# Sheet1.net
KiCad netlist of a schematic drawn in Altium Designer
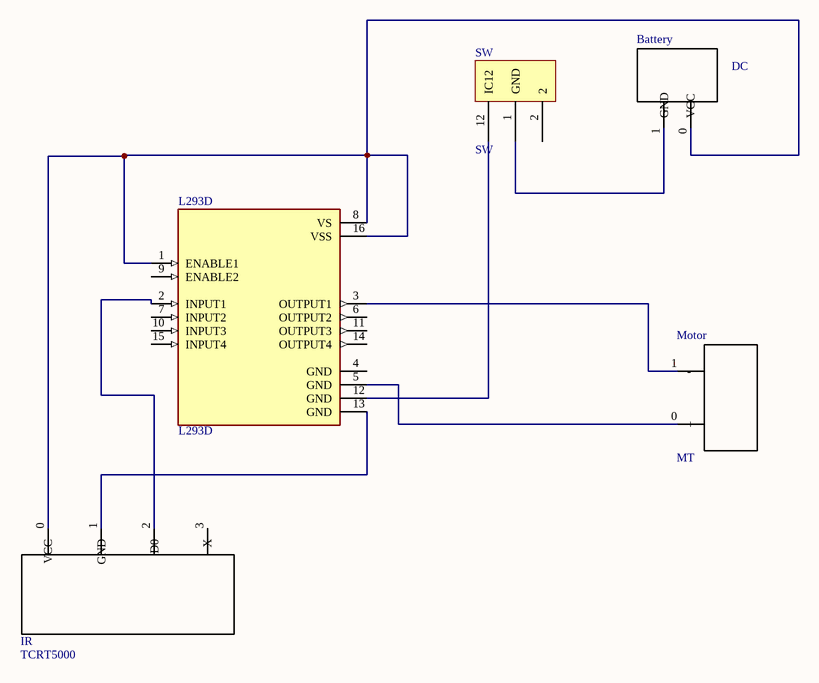
[diagram p0: Sheet1.SchDoc]

(export (version "E")
  (design (tool "Eeschema 10.0.6"))
  (components
    (comp (ref "Battery") (value "DC") (footprint "Battery") (libsource (lib "Schlib1") (part "battery")))
    (comp (ref "IR") (value "TCRT5000") (footprint "IR") (libsource (lib "Schlib1") (part "TCRT5000")))
    (comp (ref "L293D")
      (value "L293D")
      (footprint "DIP880W50P254L2000H510Q16")
      (description "Bipolar Motor Driver - Parallel 16-PowerDIP")
      (fields (field (name "MF") "STMicroelectronics"))
      (libsource (lib "Schlib1") (part "L293D"))
    )
    (comp (ref "Motor") (value "MT") (footprint "motor") (libsource (lib "Schlib1") (part "motor")))
    (comp (ref "SW") (value "SW") (footprint "SW") (libsource (lib "Schlib1") (part "SW")))
  )
  (nets
    (net (code "1") (name "Net-(Battery-GND)") (class "Default")
      (node (ref "Battery") (pin "1") (pinfunction "GND_1") (pintype "passive"))
      (node (ref "SW") (pin "1") (pinfunction "GND_1") (pintype "passive"))
    )
    (net (code "2") (name "Net-(Battery-VCC)") (class "Default")
      (node (ref "Battery") (pin "0") (pinfunction "VCC_0") (pintype "passive"))
      (node (ref "IR") (pin "0") (pinfunction "VCC_0") (pintype "power_in"))
      (node (ref "L293D") (pin "1") (pinfunction "ENABLE1_1") (pintype "input"))
      (node (ref "L293D") (pin "16") (pinfunction "VSS_16") (pintype "power_in"))
      (node (ref "L293D") (pin "8") (pinfunction "VS_8") (pintype "power_in"))
    )
    (net (code "3") (name "Net-(IR-D0)") (class "Default")
      (node (ref "IR") (pin "2") (pinfunction "D0_2") (pintype "output"))
      (node (ref "L293D") (pin "2") (pinfunction "INPUT1_2") (pintype "input"))
    )
    (net (code "4") (name "Net-(IR-GND)") (class "Default")
      (node (ref "IR") (pin "1") (pinfunction "GND_1") (pintype "power_in"))
      (node (ref "L293D") (pin "13") (pinfunction "GND_13") (pintype "power_in"))
    )
    (net (code "5") (name "Net-(L293D-OUTPUT1)") (class "Default")
      (node (ref "L293D") (pin "3") (pinfunction "OUTPUT1_3") (pintype "output"))
      (node (ref "Motor") (pin "1") (pinfunction "-_1") (pintype "passive"))
    )
    (net (code "6") (name "Net-(Motor-+)") (class "Default")
      (node (ref "L293D") (pin "5") (pinfunction "GND_5") (pintype "power_in"))
      (node (ref "Motor") (pin "0") (pinfunction "+_0") (pintype "passive"))
    )
    (net (code "7") (name "Net-(SW-IC12)") (class "Default")
      (node (ref "L293D") (pin "12") (pinfunction "GND_12") (pintype "power_in"))
      (node (ref "SW") (pin "12") (pinfunction "IC12_12") (pintype "passive"))
    )
    (net (code "8") (name "unconnected-(IR-X-Pad3)") (class "Default")
      (node (ref "IR") (pin "3") (pinfunction "X_3") (pintype "output"))
    )
    (net (code "9") (name "unconnected-(L293D-ENABLE2-Pad9)") (class "Default")
      (node (ref "L293D") (pin "9") (pinfunction "ENABLE2_9") (pintype "input"))
    )
    (net (code "10") (name "unconnected-(L293D-GND-Pad4)") (class "Default")
      (node (ref "L293D") (pin "4") (pinfunction "GND_4") (pintype "power_in"))
    )
    (net (code "11") (name "unconnected-(L293D-INPUT2-Pad7)") (class "Default")
      (node (ref "L293D") (pin "7") (pinfunction "INPUT2_7") (pintype "input"))
    )
    (net (code "12") (name "unconnected-(L293D-INPUT3-Pad10)") (class "Default")
      (node (ref "L293D") (pin "10") (pinfunction "INPUT3_10") (pintype "input"))
    )
    (net (code "13") (name "unconnected-(L293D-INPUT4-Pad15)") (class "Default")
      (node (ref "L293D") (pin "15") (pinfunction "INPUT4_15") (pintype "input"))
    )
    (net (code "14") (name "unconnected-(L293D-OUTPUT2-Pad6)") (class "Default")
      (node (ref "L293D") (pin "6") (pinfunction "OUTPUT2_6") (pintype "output"))
    )
    (net (code "15") (name "unconnected-(L293D-OUTPUT3-Pad11)") (class "Default")
      (node (ref "L293D") (pin "11") (pinfunction "OUTPUT3_11") (pintype "output"))
    )
    (net (code "16") (name "unconnected-(L293D-OUTPUT4-Pad14)") (class "Default")
      (node (ref "L293D") (pin "14") (pinfunction "OUTPUT4_14") (pintype "output"))
    )
    (net (code "17") (name "unconnected-(SW-Pad2)") (class "Default")
      (node (ref "SW") (pin "2") (pinfunction "2_2") (pintype "passive"))
    )
  )
)
